# Connector.net
KiCad netlist of a schematic drawn in Altium Designer
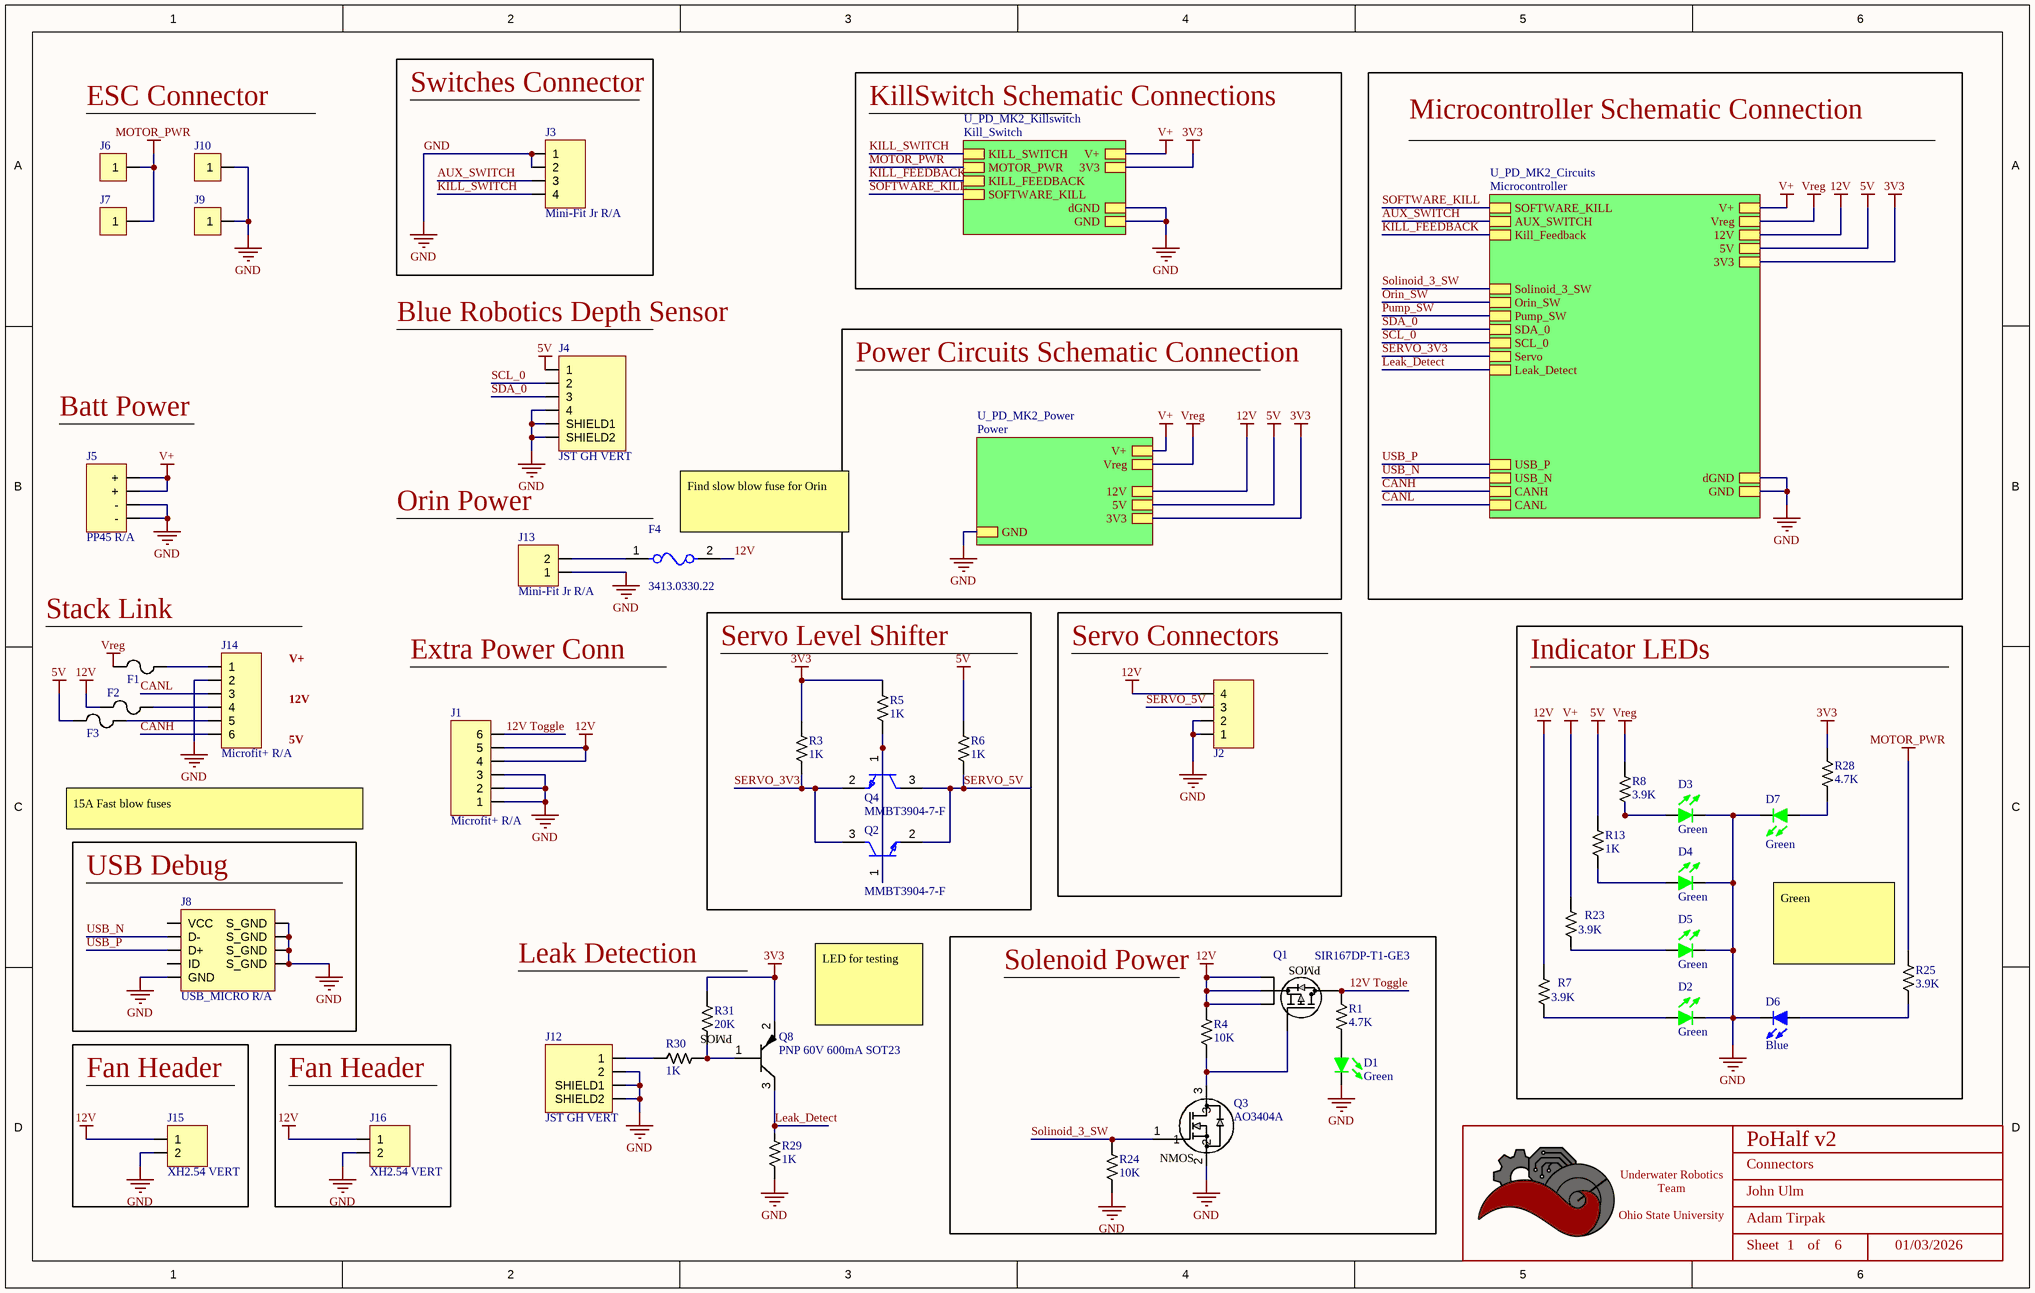
[diagram p0: Connector.SchDoc]

(export (version "E")
  (design (tool "Eeschema 10.0.6"))
  (components
    (comp (ref "D1")
      (value "IN-S63AT5G")
      (footprint "LED_0603")
      (description "LED Green Vf= 3V If = 0.005A\r\nIN-S63AT5G")
      (fields (field (name "COLOR") "Green") (field (name "MADE BY") "Robert Pafford"))
      (libsource (lib "Diodes") (part "LED_Green_0603_3V"))
    )
    (comp (ref "D2")
      (value "IN-S63AT5G")
      (footprint "LED_0603")
      (description "LED Green Vf= 3V If = 0.005A\r\nIN-S63AT5G")
      (fields (field (name "COLOR") "Green") (field (name "MADE BY") "Robert Pafford"))
      (libsource (lib "Diodes") (part "LED_Green_0603_3V"))
    )
    (comp (ref "D3")
      (value "IN-S63AT5G")
      (footprint "LED_0603")
      (description "LED Green Vf= 3V If = 0.005A\r\nIN-S63AT5G")
      (fields (field (name "COLOR") "Green") (field (name "MADE BY") "Robert Pafford"))
      (libsource (lib "Diodes") (part "LED_Green_0603_3V"))
    )
    (comp (ref "D4")
      (value "IN-S63AT5G")
      (footprint "LED_0603")
      (description "LED Green Vf= 3V If = 0.005A\r\nIN-S63AT5G")
      (fields (field (name "COLOR") "Green") (field (name "MADE BY") "Robert Pafford"))
      (libsource (lib "Diodes") (part "LED_Green_0603_3V"))
    )
    (comp (ref "D5")
      (value "IN-S63AT5G")
      (footprint "LED_0603")
      (description "LED Green Vf= 3V If = 0.005A\r\nIN-S63AT5G")
      (fields (field (name "COLOR") "Green") (field (name "MADE BY") "Robert Pafford"))
      (libsource (lib "Diodes") (part "LED_Green_0603_3V"))
    )
    (comp (ref "D6")
      (value "150060BS75000")
      (footprint "LED_0603")
      (description "LED Blue Vf= 3.2V If = 0.020A\r\n150060BS75000")
      (fields (field (name "COLOR") "Blue") (field (name "MADE BY") "Robert Pafford"))
      (libsource (lib "Diodes") (part "LED_Blue_0603"))
    )
    (comp (ref "D7")
      (value "IN-S63AT5G")
      (footprint "LED_0603")
      (description "LED Green Vf= 3V If = 0.005A\r\nIN-S63AT5G")
      (fields (field (name "COLOR") "Green") (field (name "MADE BY") "Robert Pafford"))
      (libsource (lib "Diodes") (part "LED_Green_0603_3V"))
    )
    (comp (ref "F1")
      (value "0685H9150-01")
      (footprint "0501Series_LTF")
      (description "Bel Fuse  ¦ 15A ¦ 32V DC ¦ SMD ¦ Fast Blow ¦ 1206")
      (fields (field (name "CREATED BY") "Nathan Ayer"))
      (libsource (lib "Fuses") (part "Bel Fuse 15A"))
    )
    (comp (ref "F2")
      (value "0685H9150-01")
      (footprint "0501Series_LTF")
      (description "Bel Fuse  ¦ 15A ¦ 32V DC ¦ SMD ¦ Fast Blow ¦ 1206")
      (fields (field (name "CREATED BY") "Nathan Ayer"))
      (libsource (lib "Fuses") (part "Bel Fuse 15A"))
    )
    (comp (ref "F3")
      (value "0685H9150-01")
      (footprint "0501Series_LTF")
      (description "Bel Fuse  ¦ 15A ¦ 32V DC ¦ SMD ¦ Fast Blow ¦ 1206")
      (fields (field (name "CREATED BY") "Nathan Ayer"))
      (libsource (lib "Fuses") (part "Bel Fuse 15A"))
    )
    (comp (ref "F4")
      (value "3413.0330.22")
      (footprint "FP-3413_0330_22-MFG")
      (description "FUSE BOARD MNT 15A 32VAC 63VDC")
      (fields
        (field (name "MANUFACTURER") "Schurter Inc")
        (field (name "OCTOPART") "https://octopart.com/3413.0330.22-schurter-8400836")
      )
      (libsource (lib "Altium Content Vault") (part "5bcf9b9f640e542cf0359d10258e979"))
    )
    (comp (ref "J1")
      (value "Microfit+ R/A")
      (footprint "CONN_MOLEX_MICROFIT_6_POS_R/A")
      (description "Molex Microfit+ \r\n212528 6 POS R/A Black")
      (fields (field (name "MANUFACTURER") "Molex"))
      (libsource (lib "Connectors") (part "CONN_MOLEX_MICROFIT+_6POS_R/A"))
    )
    (comp (ref "J2")
      (value "Microfit+ R/A")
      (footprint "CONN_MOLEX_MICROFIT_4_POS_R/A")
      (description "Molex Microfit+ \r\n212528 4 POS R/A Black")
      (fields (field (name "MANUFACTURER") "Molex"))
      (libsource (lib "Connectors") (part "CONN_MOLEX_MICROFIT+_4POS_R/A"))
    )
    (comp (ref "J3")
      (value "Mini-Fit Jr R/A")
      (footprint "CONN_MOLEX_MINIFIT JR_4 POS_R/A")
      (description "Molex Minifit Jr. 5569 \r\n4 Pos R/A Natural")
      (fields (field (name "MANUFACTURER") "Molex") (field (name "CREATED BY") "Flip B"))
      (libsource (lib "Connectors") (part "CONN_MOLEX_MINIFIT JR_4POS_R/A"))
    )
    (comp (ref "J4")
      (value "JST GH VERT")
      (footprint "CONN_JST_BM04B-GHS-TBT(LF)(SN)(N)")
      (description "JST GH Pitch 4 Pos Vertical")
      (fields (field (name "MANUFACTURER") "JST") (field (name "CREATED BY") "Robert P"))
      (libsource (lib "Connectors") (part "CONN_JST_GH_4POS_VERT"))
    )
    (comp (ref "J5")
      (value "PP45 R/A")
      (footprint "CONN_ANDERSON_PP45_4 POS_R/A")
      (description "Anderson PP45\r\n4 Pos R/A Red/Black")
      (fields (field (name "MANUFACTURER") "Anderson") (field (name "CREATED BY") "Flip B"))
      (libsource (lib "Connectors") (part "CONN_ANDERSON_2x2_R/A"))
    )
    (comp (ref "J6")
      (value "Redcube M4 Term 85A")
      (footprint "Redcube M4 Term 85A")
      (fields (field (name "CREATED BY") "Nahtan Ayer"))
      (libsource (lib "Connectors") (part "Redcube M4 Term 85A"))
    )
    (comp (ref "J7")
      (value "Redcube M4 Term 85A")
      (footprint "Redcube M4 Term 85A")
      (fields (field (name "CREATED BY") "Nahtan Ayer"))
      (libsource (lib "Connectors") (part "Redcube M4 Term 85A"))
    )
    (comp (ref "J8")
      (value "USB_MICRO R/A")
      (footprint "CONN_MINIUSB")
      (description "Amphenol Micro USB-B\r\nUSB2.0 5 Pin Right Angle SMD")
      (fields (field (name "MANUFACTURER") "Amphenol") (field (name "CREATED BY") "Flip B"))
      (libsource (lib "Connectors") (part "CONN_MICROUSB"))
    )
    (comp (ref "J9")
      (value "Redcube M4 Term 85A")
      (footprint "Redcube M4 Term 85A")
      (fields (field (name "CREATED BY") "Nahtan Ayer"))
      (libsource (lib "Connectors") (part "Redcube M4 Term 85A"))
    )
    (comp (ref "J10")
      (value "Redcube M4 Term 85A")
      (footprint "Redcube M4 Term 85A")
      (fields (field (name "CREATED BY") "Nahtan Ayer"))
      (libsource (lib "Connectors") (part "Redcube M4 Term 85A"))
    )
    (comp (ref "J12")
      (value "JST GH VERT")
      (footprint "CONN_JST_SM02B-GHS-TB(LF)(SN)")
      (description "JST GH Pitch 2 Pos Vertical")
      (fields (field (name "MANUFACTURER") "JST") (field (name "CREATED BY") "Robert P"))
      (libsource (lib "Connectors") (part "CONN_JST_GH_2POS_VERT"))
    )
    (comp (ref "J13")
      (value "Mini-Fit Jr R/A")
      (footprint "CONN_MOLEX_MINIFIT JR_2 POS_R/A")
      (description "Molex Minifit Jr. 5569 \r\n2 Pos R/A Natural")
      (fields (field (name "MANUFACTURER") "Molex") (field (name "CREATED BY") "Robert P"))
      (libsource (lib "Connectors") (part "CONN_MOLEX_MINIFIT JR_2POS_R/A"))
    )
    (comp (ref "J14")
      (value "Microfit+ R/A")
      (footprint "CONN_MOLEX_MICROFIT_6_POS_R/A")
      (description "Molex Microfit+ \r\n212528 6 POS R/A Black")
      (fields (field (name "MANUFACTURER") "Molex"))
      (libsource (lib "") (part "CONN_MOLEX_MICROFIT+_6POS_R/A_1"))
    )
    (comp (ref "J15")
      (value "XH2.54 VERT")
      (footprint "CONN_JST_XH254_2POS_VERT")
      (description "JST XH 2.54mm Pitch 2 Pos Vertical")
      (fields (field (name "MANUFACTURER") "JST") (field (name "CREATED BY") "Robert P"))
      (libsource (lib "Connectors") (part "CONN_JST_XH254_2POS_VERT"))
    )
    (comp (ref "J16")
      (value "XH2.54 VERT")
      (footprint "CONN_JST_XH254_2POS_VERT")
      (description "JST XH 2.54mm Pitch 2 Pos Vertical")
      (fields (field (name "MANUFACTURER") "JST") (field (name "CREATED BY") "Robert P"))
      (libsource (lib "Connectors") (part "CONN_JST_XH254_2POS_VERT"))
    )
    (comp (ref "Q1")
      (value "SIR167DP-T1-GE3")
      (footprint "MOSFET_7DP-T1-GE3_VIS")
      (description "P-Channel 30 V 60A (Tc) 65.8W (Tc) Surface Mount PowerPAK® SO-8")
      (fields (field (name "COPYRIGHT") "Copyright (C) 2022 Ultra Librarian. All rights reserved."))
      (libsource (lib "Transistors") (part "SIR167DP-T1-GE3"))
    )
    (comp (ref "Q2")
      (value "MMBT3904-7-F")
      (footprint "FP-SOT23-IPC_A")
      (description "TRANS NPN 40V 0.2A SMD SOT23-3")
      (libsource (lib "Altium Content Vault") (part "b44e953556f554d0102664c7d152cb4"))
    )
    (comp (ref "Q3")
      (value "AO3404A")
      (footprint "SOT-23-3")
      (description "N-Channel 30 V 5.8A (Ta) 1.4W (Ta) Surface Mount SOT-23-3")
      (fields (field (name "CREATED BY") "Dylan T"))
      (libsource (lib "Transistors") (part "AO3404A"))
    )
    (comp (ref "Q4")
      (value "MMBT3904-7-F")
      (footprint "FP-SOT23-IPC_A")
      (description "TRANS NPN 40V 0.2A SMD SOT23-3")
      (libsource (lib "Altium Content Vault") (part "b44e953556f554d0102664c7d152cb4"))
    )
    (comp (ref "Q8")
      (value "PNP 60V 600mA SOT23")
      (footprint "SOT-23-3")
      (description "PNP 60 V 600mA Surface Mount SOT-23")
      (fields
        (field (name "MANUFACTURER_PART_NUMBER") "MMBT2907A-7-F")
        (field (name "CREATED BY") "Robert Pafford")
      )
      (libsource (lib "Transistors") (part "MMBT2907A-7-F"))
    )
    (comp (ref "R1")
      (value "4.7k Ohm 5% 1/10W")
      (footprint "RESISTOR_0603")
      (description "RES 4.7k OHM 5% 1/10W 0603")
      (fields
        (field (name "TOLERANCE") "+/- 5%")
        (field (name "VALUE  (OHMS)") "4.7K")
        (field (name "MADE BY") "Robert Pafford")
      )
      (libsource (lib "Resistors") (part "RESISTOR_4.7K_0603"))
    )
    (comp (ref "R3")
      (value "1k Ohm 5% 1/8W")
      (footprint "RESISTOR_0603")
      (description "RES 1k OHM 5% 1/8W 0603")
      (fields
        (field (name "TOLERANCE") "+/- 5%")
        (field (name "VALUE  (OHMS)") "1K")
        (field (name "MADE BY") "Robert Pafford")
      )
      (libsource (lib "Resistors") (part "RESISTOR_1K_0603"))
    )
    (comp (ref "R4")
      (value "10k Ohm 5% 1/10W")
      (footprint "RESISTOR_0603")
      (description "RES 10k OHM 5% 1/10W 0603")
      (fields
        (field (name "TOLERANCE") "+/- 5%")
        (field (name "VALUE  (OHMS)") "10K")
        (field (name "MADE BY") "Robert Pafford")
      )
      (libsource (lib "Resistors") (part "RESISTOR_10K_0603"))
    )
    (comp (ref "R5")
      (value "1k Ohm 5% 1/8W")
      (footprint "RESISTOR_0603")
      (description "RES 1k OHM 5% 1/8W 0603")
      (fields
        (field (name "TOLERANCE") "+/- 5%")
        (field (name "VALUE  (OHMS)") "1K")
        (field (name "MADE BY") "Robert Pafford")
      )
      (libsource (lib "Resistors") (part "RESISTOR_1K_0603"))
    )
    (comp (ref "R6")
      (value "1k Ohm 5% 1/8W")
      (footprint "RESISTOR_0603")
      (description "RES 1k OHM 5% 1/8W 0603")
      (fields
        (field (name "TOLERANCE") "+/- 5%")
        (field (name "VALUE  (OHMS)") "1K")
        (field (name "MADE BY") "Robert Pafford")
      )
      (libsource (lib "Resistors") (part "RESISTOR_1K_0603"))
    )
    (comp (ref "R7")
      (value "3.9k Ohm 5% 1/10W")
      (footprint "RESISTOR_0603")
      (description "RES 3.9k OHM 1% 1/10W 0603")
      (fields
        (field (name "TOLERANCE") "+/- 1%")
        (field (name "VALUE  (OHMS)") "3.9K")
        (field (name "MADE BY") "Robert Pafford")
      )
      (libsource (lib "Resistors") (part "RESISTOR_3.9K_0603"))
    )
    (comp (ref "R8")
      (value "3.9k Ohm 5% 1/10W")
      (footprint "RESISTOR_0603")
      (description "RES 3.9k OHM 1% 1/10W 0603")
      (fields
        (field (name "TOLERANCE") "+/- 1%")
        (field (name "VALUE  (OHMS)") "3.9K")
        (field (name "MADE BY") "Robert Pafford")
      )
      (libsource (lib "Resistors") (part "RESISTOR_3.9K_0603"))
    )
    (comp (ref "R13")
      (value "1k Ohm 5% 1/8W")
      (footprint "RESISTOR_0603")
      (description "RES 1k OHM 5% 1/8W 0603")
      (fields
        (field (name "TOLERANCE") "+/- 5%")
        (field (name "VALUE  (OHMS)") "1K")
        (field (name "MADE BY") "Robert Pafford")
      )
      (libsource (lib "Resistors") (part "RESISTOR_1K_0603"))
    )
    (comp (ref "R23")
      (value "3.9k Ohm 5% 1/10W")
      (footprint "RESISTOR_0603")
      (description "RES 3.9k OHM 1% 1/10W 0603")
      (fields
        (field (name "TOLERANCE") "+/- 1%")
        (field (name "VALUE  (OHMS)") "3.9K")
        (field (name "MADE BY") "Robert Pafford")
      )
      (libsource (lib "Resistors") (part "RESISTOR_3.9K_0603"))
    )
    (comp (ref "R24")
      (value "10k Ohm 5% 1/10W")
      (footprint "RESISTOR_0603")
      (description "RES 10k OHM 5% 1/10W 0603")
      (fields
        (field (name "TOLERANCE") "+/- 5%")
        (field (name "VALUE  (OHMS)") "10K")
        (field (name "MADE BY") "Robert Pafford")
      )
      (libsource (lib "Resistors") (part "RESISTOR_10K_0603"))
    )
    (comp (ref "R25")
      (value "3.9k Ohm 5% 1/10W")
      (footprint "RESISTOR_0603")
      (description "RES 3.9k OHM 1% 1/10W 0603")
      (fields
        (field (name "TOLERANCE") "+/- 1%")
        (field (name "VALUE  (OHMS)") "3.9K")
        (field (name "MADE BY") "Robert Pafford")
      )
      (libsource (lib "Resistors") (part "RESISTOR_3.9K_0603"))
    )
    (comp (ref "R28")
      (value "4.7k Ohm 5% 1/10W")
      (footprint "RESISTOR_0603")
      (description "RES 4.7k OHM 5% 1/10W 0603")
      (fields
        (field (name "TOLERANCE") "+/- 5%")
        (field (name "VALUE  (OHMS)") "4.7K")
        (field (name "MADE BY") "Robert Pafford")
      )
      (libsource (lib "Resistors") (part "RESISTOR_4.7K_0603"))
    )
    (comp (ref "R29")
      (value "1k Ohm 5% 1/8W")
      (footprint "RESISTOR_0603")
      (description "RES 1k OHM 5% 1/8W 0603")
      (fields
        (field (name "TOLERANCE") "+/- 5%")
        (field (name "VALUE  (OHMS)") "1K")
        (field (name "MADE BY") "Robert Pafford")
      )
      (libsource (lib "Resistors") (part "RESISTOR_1K_0603"))
    )
    (comp (ref "R30")
      (value "1k Ohm 5% 1/8W")
      (footprint "RESISTOR_0603")
      (description "RES 1k OHM 5% 1/8W 0603")
      (fields
        (field (name "TOLERANCE") "+/- 5%")
        (field (name "VALUE  (OHMS)") "1K")
        (field (name "MADE BY") "Robert Pafford")
      )
      (libsource (lib "Resistors") (part "RESISTOR_1K_0603"))
    )
    (comp (ref "R31")
      (value "20k Ohm 1% 1/16W")
      (footprint "RESISTOR_0402")
      (description "RES 20k OHM 1% 1/16W 0402")
      (fields
        (field (name "TOLERANCE") "+/- 1%")
        (field (name "VALUE  (OHMS)") "20K")
        (field (name "MADE BY") "Robert Pafford")
      )
      (libsource (lib "Resistors") (part "RESISTOR_20K_0402"))
    )
  )
  (nets
    (net (code "1") (name "/12V Toggle") (class "Default")
      (node (ref "J1") (pin "6") (pinfunction "6_6") (pintype "passive"))
      (node (ref "Q1") (pin "D") (pinfunction "D_D") (pintype "passive"))
      (node (ref "R1") (pin "2") (pinfunction "2_2") (pintype "passive"))
    )
    (net (code "2") (name "/AUX_SWITCH") (class "Default")
      (node (ref "J3") (pin "3") (pinfunction "3_3") (pintype "passive"))
    )
    (net (code "3") (name "/CANH") (class "Default")
      (node (ref "J14") (pin "6") (pinfunction "6_6") (pintype "passive"))
    )
    (net (code "4") (name "/CANL") (class "Default")
      (node (ref "J14") (pin "3") (pinfunction "3_3") (pintype "passive"))
    )
    (net (code "6") (name "/KILL_SWITCH") (class "Default")
      (node (ref "J3") (pin "4") (pinfunction "4_4") (pintype "passive"))
    )
    (net (code "7") (name "/Leak_Detect") (class "Default")
      (node (ref "Q8") (pin "3") (pinfunction "3_3") (pintype "passive"))
      (node (ref "R29") (pin "1") (pinfunction "1_1") (pintype "passive"))
    )
    (net (code "10") (name "/SCL_0") (class "Default")
      (node (ref "J4") (pin "2") (pinfunction "2_2") (pintype "passive"))
    )
    (net (code "11") (name "/SDA_0") (class "Default")
      (node (ref "J4") (pin "3") (pinfunction "3_3") (pintype "passive"))
    )
    (net (code "12") (name "/SERVO_3V3") (class "Default")
      (node (ref "Q2") (pin "3") (pinfunction "C_3") (pintype "passive"))
      (node (ref "Q4") (pin "2") (pinfunction "E_2") (pintype "passive"))
      (node (ref "R3") (pin "2") (pinfunction "2_2") (pintype "passive"))
    )
    (net (code "13") (name "/SERVO_5V") (class "Default")
      (node (ref "J2") (pin "3") (pinfunction "3_3") (pintype "passive"))
      (node (ref "Q2") (pin "2") (pinfunction "E_2") (pintype "passive"))
      (node (ref "Q4") (pin "3") (pinfunction "C_3") (pintype "passive"))
      (node (ref "R6") (pin "2") (pinfunction "2_2") (pintype "passive"))
    )
    (net (code "15") (name "/Solinoid_3_SW") (class "Default")
      (node (ref "Q3") (pin "1") (pinfunction "1_1") (pintype "passive"))
      (node (ref "R24") (pin "1") (pinfunction "1_1") (pintype "passive"))
    )
    (net (code "16") (name "/USB_N") (class "Default")
      (node (ref "J8") (pin "2") (pinfunction "D-_2") (pintype "passive"))
    )
    (net (code "17") (name "/USB_P") (class "Default")
      (node (ref "J8") (pin "3") (pinfunction "D+_3") (pintype "passive"))
    )
    (net (code "18") (name "3V3") (class "Default")
      (node (ref "Q8") (pin "2") (pinfunction "2_2") (pintype "passive"))
      (node (ref "R28") (pin "2") (pinfunction "2_2") (pintype "passive"))
      (node (ref "R3") (pin "1") (pinfunction "1_1") (pintype "passive"))
      (node (ref "R31") (pin "1") (pinfunction "1_1") (pintype "passive"))
      (node (ref "R5") (pin "1") (pinfunction "1_1") (pintype "passive"))
    )
    (net (code "19") (name "5V") (class "Default")
      (node (ref "F3") (pin "1") (pinfunction "1_1") (pintype "passive"))
      (node (ref "J4") (pin "1") (pinfunction "1_1") (pintype "passive"))
      (node (ref "R13") (pin "1") (pinfunction "1_1") (pintype "passive"))
      (node (ref "R6") (pin "1") (pinfunction "1_1") (pintype "passive"))
    )
    (net (code "20") (name "12V") (class "Default")
      (node (ref "F2") (pin "1") (pinfunction "1_1") (pintype "passive"))
      (node (ref "F4") (pin "2") (pinfunction "2_2") (pintype "passive"))
      (node (ref "J1") (pin "4") (pinfunction "4_4") (pintype "passive"))
      (node (ref "J1") (pin "5") (pinfunction "5_5") (pintype "passive"))
      (node (ref "J15") (pin "1") (pinfunction "1_1") (pintype "passive"))
      (node (ref "J16") (pin "1") (pinfunction "1_1") (pintype "passive"))
      (node (ref "J2") (pin "4") (pinfunction "4_4") (pintype "passive"))
      (node (ref "Q1") (pin "1") (pinfunction "S_1") (pintype "passive"))
      (node (ref "Q1") (pin "2") (pinfunction "S_2") (pintype "passive"))
      (node (ref "Q1") (pin "3") (pinfunction "S_3") (pintype "passive"))
      (node (ref "R4") (pin "1") (pinfunction "1_1") (pintype "passive"))
      (node (ref "R7") (pin "1") (pinfunction "1_1") (pintype "passive"))
    )
    (net (code "21") (name "GND") (class "Default")
      (node (ref "D1") (pin "2") (pinfunction "2_2") (pintype "passive"))
      (node (ref "D2") (pin "2") (pinfunction "2_2") (pintype "passive"))
      (node (ref "D3") (pin "2") (pinfunction "2_2") (pintype "passive"))
      (node (ref "D4") (pin "2") (pinfunction "2_2") (pintype "passive"))
      (node (ref "D5") (pin "2") (pinfunction "2_2") (pintype "passive"))
      (node (ref "D6") (pin "2") (pinfunction "2_2") (pintype "passive"))
      (node (ref "D7") (pin "2") (pinfunction "2_2") (pintype "passive"))
      (node (ref "J1") (pin "1") (pinfunction "1_1") (pintype "passive"))
      (node (ref "J1") (pin "2") (pinfunction "2_2") (pintype "passive"))
      (node (ref "J1") (pin "3") (pinfunction "3_3") (pintype "passive"))
      (node (ref "J10") (pin "1") (pinfunction "1_1") (pintype "passive"))
      (node (ref "J12") (pin "2") (pinfunction "2_2") (pintype "passive"))
      (node (ref "J12") (pin "S1") (pinfunction "SHIELD1_S1") (pintype "passive"))
      (node (ref "J12") (pin "S2") (pinfunction "SHIELD2_S2") (pintype "passive"))
      (node (ref "J13") (pin "1") (pinfunction "1_1") (pintype "passive"))
      (node (ref "J14") (pin "2") (pinfunction "2_2") (pintype "passive"))
      (node (ref "J15") (pin "2") (pinfunction "2_2") (pintype "passive"))
      (node (ref "J16") (pin "2") (pinfunction "2_2") (pintype "passive"))
      (node (ref "J2") (pin "1") (pinfunction "1_1") (pintype "passive"))
      (node (ref "J2") (pin "2") (pinfunction "2_2") (pintype "passive"))
      (node (ref "J3") (pin "1") (pinfunction "1_1") (pintype "passive"))
      (node (ref "J3") (pin "2") (pinfunction "2_2") (pintype "passive"))
      (node (ref "J4") (pin "4") (pinfunction "4_4") (pintype "passive"))
      (node (ref "J4") (pin "S1") (pinfunction "SHIELD1_S1") (pintype "passive"))
      (node (ref "J4") (pin "S2") (pinfunction "SHIELD2_S2") (pintype "passive"))
      (node (ref "J5") (pin "3") (pinfunction "-_3") (pintype "passive"))
      (node (ref "J5") (pin "4") (pinfunction "-_4") (pintype "passive"))
      (node (ref "J8") (pin "5") (pinfunction "GND_5") (pintype "passive"))
      (node (ref "J8") (pin "6") (pinfunction "S_GND_6") (pintype "passive"))
      (node (ref "J8") (pin "7") (pinfunction "S_GND_7") (pintype "passive"))
      (node (ref "J8") (pin "8") (pinfunction "S_GND_8") (pintype "passive"))
      (node (ref "J8") (pin "9") (pinfunction "S_GND_9") (pintype "passive"))
      (node (ref "J9") (pin "1") (pinfunction "1_1") (pintype "passive"))
      (node (ref "Q3") (pin "2") (pinfunction "2_2") (pintype "passive"))
      (node (ref "R24") (pin "2") (pinfunction "2_2") (pintype "passive"))
      (node (ref "R29") (pin "2") (pinfunction "2_2") (pintype "passive"))
    )
    (net (code "22") (name "MOTOR_PWR") (class "Default")
      (node (ref "J6") (pin "1") (pinfunction "1_1") (pintype "passive"))
      (node (ref "J7") (pin "1") (pinfunction "1_1") (pintype "passive"))
      (node (ref "R25") (pin "1") (pinfunction "1_1") (pintype "passive"))
    )
    (net (code "23") (name "Net-(D1-Pad1)") (class "Default")
      (node (ref "D1") (pin "1") (pinfunction "1_1") (pintype "passive"))
      (node (ref "R1") (pin "1") (pinfunction "1_1") (pintype "passive"))
    )
    (net (code "24") (name "Net-(D2-Pad1)") (class "Default")
      (node (ref "D2") (pin "1") (pinfunction "1_1") (pintype "passive"))
      (node (ref "R7") (pin "2") (pinfunction "2_2") (pintype "passive"))
    )
    (net (code "25") (name "Net-(D3-Pad1)") (class "Default")
      (node (ref "D3") (pin "1") (pinfunction "1_1") (pintype "passive"))
      (node (ref "R8") (pin "2") (pinfunction "2_2") (pintype "passive"))
    )
    (net (code "26") (name "Net-(D4-Pad1)") (class "Default")
      (node (ref "D4") (pin "1") (pinfunction "1_1") (pintype "passive"))
      (node (ref "R13") (pin "2") (pinfunction "2_2") (pintype "passive"))
    )
    (net (code "27") (name "Net-(D5-Pad1)") (class "Default")
      (node (ref "D5") (pin "1") (pinfunction "1_1") (pintype "passive"))
      (node (ref "R23") (pin "2") (pinfunction "2_2") (pintype "passive"))
    )
    (net (code "28") (name "Net-(D6-Pad1)") (class "Default")
      (node (ref "D6") (pin "1") (pinfunction "1_1") (pintype "passive"))
      (node (ref "R25") (pin "2") (pinfunction "2_2") (pintype "passive"))
    )
    (net (code "29") (name "Net-(D7-Pad1)") (class "Default")
      (node (ref "D7") (pin "1") (pinfunction "1_1") (pintype "passive"))
      (node (ref "R28") (pin "1") (pinfunction "1_1") (pintype "passive"))
    )
    (net (code "30") (name "Net-(F1-Pad2)") (class "Default")
      (node (ref "F1") (pin "2") (pinfunction "2_2") (pintype "passive"))
      (node (ref "J14") (pin "1") (pinfunction "1_1") (pintype "passive"))
    )
    (net (code "31") (name "Net-(F2-Pad2)") (class "Default")
      (node (ref "F2") (pin "2") (pinfunction "2_2") (pintype "passive"))
      (node (ref "J14") (pin "4") (pinfunction "4_4") (pintype "passive"))
    )
    (net (code "32") (name "Net-(F3-Pad2)") (class "Default")
      (node (ref "F3") (pin "2") (pinfunction "2_2") (pintype "passive"))
      (node (ref "J14") (pin "5") (pinfunction "5_5") (pintype "passive"))
    )
    (net (code "33") (name "Net-(F4-Pad1)") (class "Default")
      (node (ref "F4") (pin "1") (pinfunction "1_1") (pintype "passive"))
      (node (ref "J13") (pin "2") (pinfunction "2_2") (pintype "passive"))
    )
    (net (code "34") (name "Net-(J12-Pad1)") (class "Default")
      (node (ref "J12") (pin "1") (pinfunction "1_1") (pintype "passive"))
      (node (ref "R30") (pin "2") (pinfunction "2_2") (pintype "passive"))
    )
    (net (code "35") (name "Net-(Q1-G)") (class "Default")
      (node (ref "Q1") (pin "4") (pinfunction "G_4") (pintype "passive"))
      (node (ref "Q3") (pin "3") (pinfunction "3_3") (pintype "passive"))
      (node (ref "R4") (pin "2") (pinfunction "2_2") (pintype "passive"))
    )
    (net (code "36") (name "Net-(Q2-B)") (class "Default")
      (node (ref "Q2") (pin "1") (pinfunction "B_1") (pintype "passive"))
      (node (ref "Q4") (pin "1") (pinfunction "B_1") (pintype "passive"))
      (node (ref "R5") (pin "2") (pinfunction "2_2") (pintype "passive"))
    )
    (net (code "37") (name "Net-(Q8-Pad1)") (class "Default")
      (node (ref "Q8") (pin "1") (pinfunction "1_1") (pintype "passive"))
      (node (ref "R30") (pin "1") (pinfunction "1_1") (pintype "passive"))
      (node (ref "R31") (pin "2") (pinfunction "2_2") (pintype "passive"))
    )
    (net (code "38") (name "V+") (class "Default")
      (node (ref "J5") (pin "1") (pinfunction "+_1") (pintype "passive"))
      (node (ref "J5") (pin "2") (pinfunction "+_2") (pintype "passive"))
      (node (ref "R23") (pin "1") (pinfunction "1_1") (pintype "passive"))
    )
    (net (code "39") (name "Vreg") (class "Default")
      (node (ref "F1") (pin "1") (pinfunction "1_1") (pintype "passive"))
      (node (ref "R8") (pin "1") (pinfunction "1_1") (pintype "passive"))
    )
    (net (code "40") (name "unconnected-(J8-ID-Pad4)") (class "Default")
      (node (ref "J8") (pin "4") (pinfunction "ID_4") (pintype "passive"))
    )
    (net (code "41") (name "unconnected-(J8-VCC-Pad1)") (class "Default")
      (node (ref "J8") (pin "1") (pinfunction "VCC_1") (pintype "passive"))
    )
  )
)
